# SAMV71_Xplained_Ultra_MCU_Peripherals.net
KiCad netlist of a schematic drawn in Altium Designer
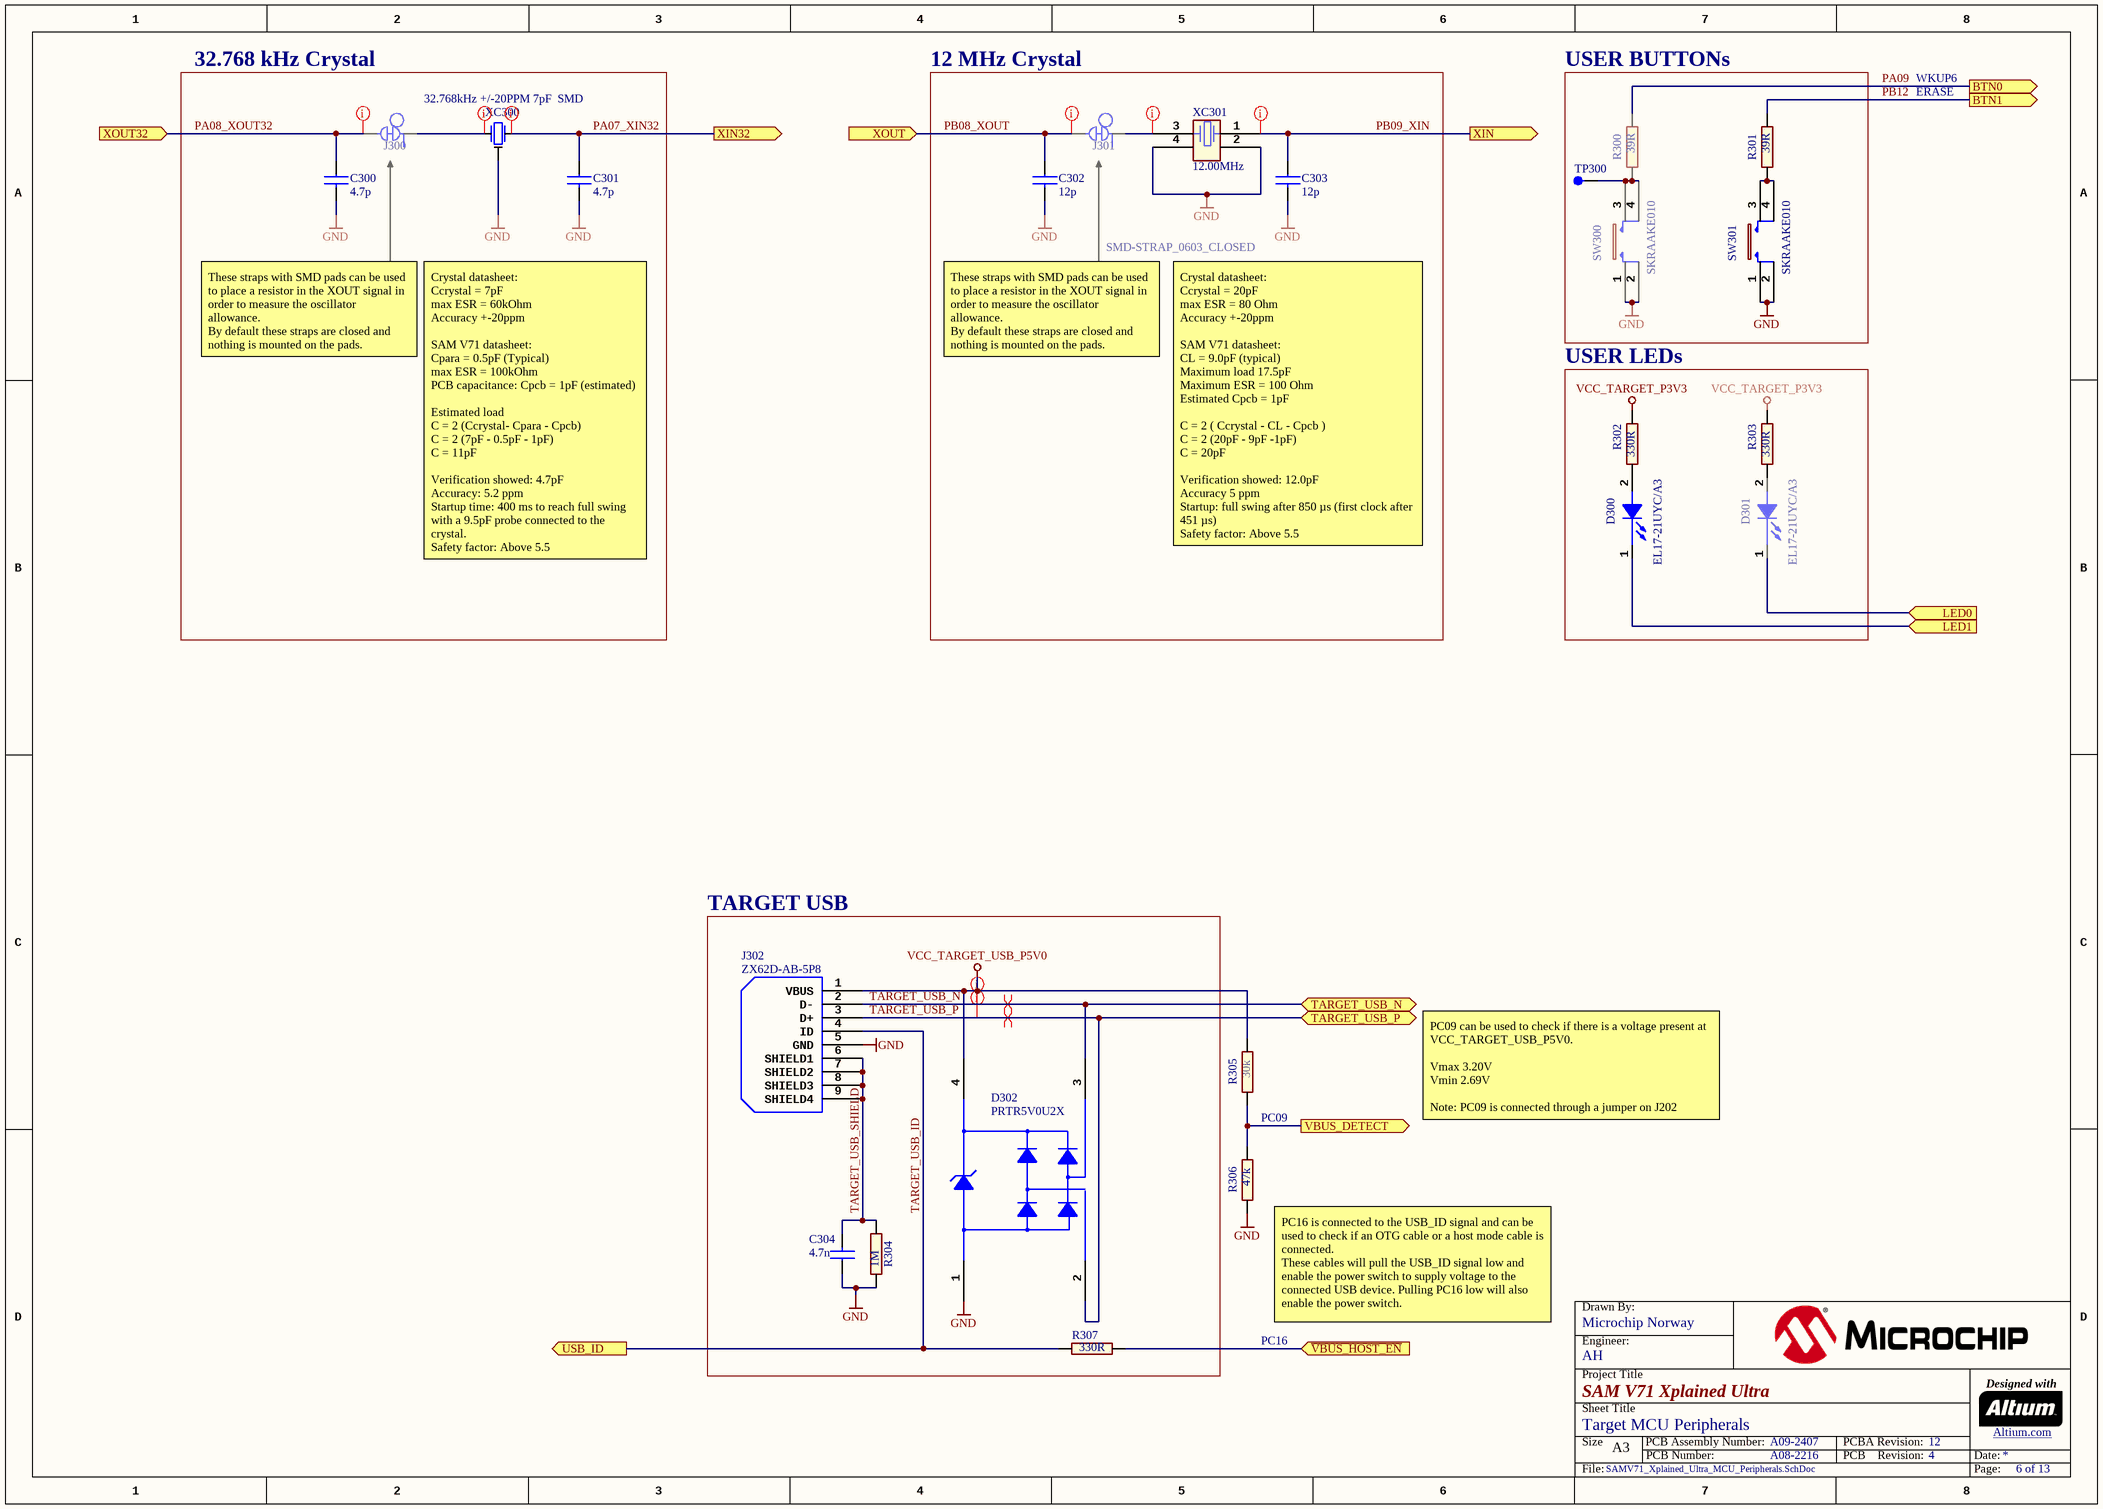
[diagram p0: SAMV71_Xplained_Ultra_MCU_Peripherals.SchDoc]

(export (version "E")
  (design (tool "Eeschema 10.0.6"))
  (components
    (comp (ref "C300")
      (value "4.7p")
      (footprint "AP1-00001")
      (description "Ceramic capacitor, SMD 0402, NP0, 50V, +/-0.25pF")
      (fields (field (name "TOLERANCE") "50V, +/-0.25pF") (field (name "MANUFACTURER") "YAGEO CORP"))
      (libsource (lib "AltiumDbLib") (part "CAP-NONPOL"))
    )
    (comp (ref "C301")
      (value "4.7p")
      (footprint "AP1-00001")
      (description "Ceramic capacitor, SMD 0402, NP0, 50V, +/-0.25pF")
      (fields (field (name "TOLERANCE") "50V, +/-0.25pF") (field (name "MANUFACTURER") "YAGEO CORP"))
      (libsource (lib "AltiumDbLib") (part "CAP-NONPOL"))
    )
    (comp (ref "C302")
      (value "12p")
      (footprint "AP1-00001")
      (description "Ceramic capacitor, SMD 0402, NP0, 50V, +/-5%")
      (fields (field (name "TOLERANCE") "50V, +/-5%") (field (name "MANUFACTURER") "Kemet"))
      (libsource (lib "AltiumDbLib") (part "CAP-NONPOL"))
    )
    (comp (ref "C303")
      (value "12p")
      (footprint "AP1-00001")
      (description "Ceramic capacitor, SMD 0402, NP0, 50V, +/-5%")
      (fields (field (name "TOLERANCE") "50V, +/-5%") (field (name "MANUFACTURER") "Kemet"))
      (libsource (lib "AltiumDbLib") (part "CAP-NONPOL"))
    )
    (comp (ref "C304")
      (value "4.7n")
      (footprint "AP1-00053")
      (description "Ceramic capacitor, SMD 0402, X7R, 25V, +/-10%")
      (fields (field (name "TOLERANCE") "25V, +/-10%") (field (name "MANUFACTURER") "PHYCOMP"))
      (libsource (lib "AltiumDbLib") (part "CAP-NONPOL"))
    )
    (comp (ref "D300")
      (value "EL17-21UYC/A3")
      (footprint "AP4-00013")
      (description "LED, Yellow, Wave length=591nm, SMD 0805, ±70°")
      (fields (field (name "MANUFACTURER") "Everlight") (field (name "MPN") "17-21UYC/S530-A3/TR8"))
      (libsource (lib "AltiumDbLib") (part "LED_12"))
    )
    (comp (ref "D301")
      (value "EL17-21UYC/A3")
      (footprint "AP4-00013")
      (description "LED, Yellow, Wave length=591nm, SMD 0805, ±70°")
      (fields (field (name "MANUFACTURER") "Everlight") (field (name "MPN") "17-21UYC/S530-A3/TR8"))
      (libsource (lib "AltiumDbLib") (part "LED_12"))
    )
    (comp (ref "D302")
      (value "PRTR5V0U2X")
      (footprint "AP4-00001")
      (description "Double rail-to-rail USB ESD protection diode")
      (fields (field (name "MANUFACTURER") "NXP"))
      (libsource (lib "AltiumDbLib") (part "PRTR5V0U2X"))
    )
    (comp (ref "J300")
      (value "~")
      (footprint "AP9-00044")
      (description "Default closed SMD strap, 0603 size")
      (libsource (lib "AltiumDbLib") (part "SMD-STRAP_CLOSED"))
    )
    (comp (ref "J301")
      (value "SMD-STRAP_0603_CLOSED")
      (footprint "AP9-00044")
      (description "Default closed SMD strap, 0603 size")
      (libsource (lib "AltiumDbLib") (part "SMD-STRAP_CLOSED"))
    )
    (comp (ref "J302")
      (value "ZX62D-AB-5P8")
      (footprint "AP8-00852")
      (description "Micro USB AB Connector, Standard SMT + DIP")
      (fields (field (name "MANUFACTURER") "HIROSE") (field (name "MPN") "ZX62D-AB-5P8(30)"))
      (libsource (lib "AltiumDbLib") (part "USB_AB"))
    )
    (comp (ref "R300")
      (value "39R")
      (footprint "AP2-00011")
      (description "Thick film resistor, SMD 0402, 1/16W, 1%")
      (fields (field (name "TOLERANCE") "1 %") (field (name "MANUFACTURER") "ASJ"))
      (libsource (lib "") (part "R2_1"))
    )
    (comp (ref "R301")
      (value "39R")
      (footprint "AP2-00011")
      (description "Thick film resistor, SMD 0402, 1/16W, 1%")
      (fields (field (name "TOLERANCE") "1 %") (field (name "MANUFACTURER") "ASJ"))
      (libsource (lib "") (part "R2_1"))
    )
    (comp (ref "R302")
      (value "330R")
      (footprint "AP2-00000")
      (description "Thick film resistor, SMD 0402, 1/16W, 1%")
      (fields (field (name "TOLERANCE") "1 %") (field (name "MANUFACTURER") "ASJ"))
      (libsource (lib "AltiumDbLib") (part "R2"))
    )
    (comp (ref "R303")
      (value "330R")
      (footprint "AP2-00000")
      (description "Thick film resistor, SMD 0402, 1/16W, 1%")
      (fields (field (name "TOLERANCE") "1 %") (field (name "MANUFACTURER") "ASJ"))
      (libsource (lib "AltiumDbLib") (part "R2"))
    )
    (comp (ref "R304")
      (value "1M")
      (footprint "AP2-00011")
      (description "Thick film resistor, SMD 0402, 1/16W, 1%")
      (fields (field (name "TOLERANCE") "1 %") (field (name "MANUFACTURER") "ASJ"))
      (libsource (lib "") (part "R2_1"))
    )
    (comp (ref "R305")
      (value "30k")
      (footprint "AP2-00000")
      (description "Thick film resistor, SMD 0402, 1/16W, 1%")
      (fields (field (name "TOLERANCE") "1 %") (field (name "MANUFACTURER") "ASJ"))
      (libsource (lib "AltiumDbLib") (part "R2"))
    )
    (comp (ref "R306")
      (value "47k")
      (footprint "AP2-00000")
      (description "Thick film resistor, SMD 0402, 1/16W, 1%")
      (fields (field (name "TOLERANCE") "1 %") (field (name "MANUFACTURER") "KOA"))
      (libsource (lib "AltiumDbLib") (part "R2"))
    )
    (comp (ref "R307")
      (value "330R")
      (footprint "AP2-00000")
      (description "Thick film resistor, SMD 0402, 1/16W, 1%")
      (fields (field (name "TOLERANCE") "1 %") (field (name "MANUFACTURER") "ASJ"))
      (libsource (lib "") (part "R2_2"))
    )
    (comp (ref "SW300")
      (value "SKRAAKE010")
      (footprint "AP8-00137")
      (description "6.2x6.2 mm SMD tact switch, same as A08-0091 but less force is needed")
      (fields (field (name "MANUFACTURER") "ALPS"))
      (libsource (lib "AltiumDbLib") (part "PUSHBUTTON1"))
    )
    (comp (ref "SW301")
      (value "SKRAAKE010")
      (footprint "AP8-00137")
      (description "6.2x6.2 mm SMD tact switch, same as A08-0091 but less force is needed")
      (fields (field (name "MANUFACTURER") "ALPS"))
      (libsource (lib "AltiumDbLib") (part "PUSHBUTTON1"))
    )
    (comp (ref "TP300")
      (value "~")
      (footprint "AP8-00010")
      (description "Single SMD testpad")
      (libsource (lib "AltiumDbLib") (part "TESTPOINT"))
    )
    (comp (ref "XC300")
      (value "32.768kHz +/-20PPM 7pF  SMD")
      (footprint "AP7-00044")
      (description "32k768 crystal, +-20ppm, CL=7pF, max ESR 60kOhm, SMD")
      (fields (field (name "TOLERANCE") "+/- 20 PPM") (field (name "MANUFACTURER") "Micro Crystal"))
      (libsource (lib "AltiumDbLib") (part "CRYSTAL_2P_metal"))
    )
    (comp (ref "XC301")
      (value "12.00MHz")
      (footprint "AP7-00039")
      (description "Fox FQ5032B 12.0MHz SMD crystal 738B-12")
      (fields (field (name "TOLERANCE") "Â±30ppm") (field (name "MANUFACTURER") "Fox  Electronics"))
      (libsource (lib "AltiumDbLib") (part "CRYSTAL1324"))
    )
  )
  (nets
    (net (code "1") (name "/LED0") (class "Default")
      (node (ref "D301") (pin "1") (pinfunction "CATHODE_1") (pintype "passive"))
    )
    (net (code "2") (name "/LED1") (class "Default")
      (node (ref "D300") (pin "1") (pinfunction "CATHODE_1") (pintype "passive"))
    )
    (net (code "3") (name "/PA07_XIN32") (class "Default")
      (node (ref "C301") (pin "1") (pinfunction "1_1") (pintype "passive"))
      (node (ref "XC300") (pin "2") (pinfunction "2_2") (pintype "passive"))
    )
    (net (code "4") (name "/PA08_XOUT32") (class "Default")
      (node (ref "C300") (pin "1") (pinfunction "1_1") (pintype "passive"))
      (node (ref "J300") (pin "2") (pinfunction "2_2") (pintype "passive"))
    )
    (net (code "5") (name "/PA09") (class "Default")
      (node (ref "R300") (pin "2") (pinfunction "2_2") (pintype "passive"))
    )
    (net (code "6") (name "/PB08_XOUT") (class "Default")
      (node (ref "C302") (pin "1") (pinfunction "1_1") (pintype "passive"))
      (node (ref "J301") (pin "2") (pinfunction "2_2") (pintype "passive"))
    )
    (net (code "7") (name "/PB09_XIN") (class "Default")
      (node (ref "C303") (pin "1") (pinfunction "1_1") (pintype "passive"))
      (node (ref "XC301") (pin "1") (pinfunction "1_1") (pintype "passive"))
    )
    (net (code "8") (name "/PB12") (class "Default")
      (node (ref "R301") (pin "2") (pinfunction "2_2") (pintype "passive"))
    )
    (net (code "9") (name "/TARGET_USB_ID") (class "Default")
      (node (ref "J302") (pin "4") (pinfunction "ID_4") (pintype "passive"))
      (node (ref "R307") (pin "1") (pinfunction "1_1") (pintype "passive"))
    )
    (net (code "10") (name "/TARGET_USB_N") (class "Default")
      (node (ref "D302") (pin "3") (pinfunction "I/O_2_3") (pintype "passive"))
      (node (ref "J302") (pin "2") (pinfunction "D-_2") (pintype "passive"))
    )
    (net (code "11") (name "/TARGET_USB_P") (class "Default")
      (node (ref "D302") (pin "2") (pinfunction "I/O_1_2") (pintype "passive"))
      (node (ref "J302") (pin "3") (pinfunction "D+_3") (pintype "passive"))
    )
    (net (code "12") (name "/TARGET_USB_SHIELD") (class "Default")
      (node (ref "C304") (pin "2") (pinfunction "2_2") (pintype "passive"))
      (node (ref "J302") (pin "6") (pinfunction "SHIELD1_6") (pintype "passive"))
      (node (ref "J302") (pin "7") (pinfunction "SHIELD2_7") (pintype "passive"))
      (node (ref "J302") (pin "8") (pinfunction "SHIELD3_8") (pintype "passive"))
      (node (ref "J302") (pin "9") (pinfunction "SHIELD4_9") (pintype "passive"))
      (node (ref "R304") (pin "2") (pinfunction "2_2") (pintype "passive"))
    )
    (net (code "13") (name "/VBUS_DETECT") (class "Default")
      (node (ref "R305") (pin "1") (pinfunction "1_1") (pintype "passive"))
      (node (ref "R306") (pin "2") (pinfunction "2_2") (pintype "passive"))
    )
    (net (code "14") (name "/~{VBUS_HOST_EN}") (class "Default")
      (node (ref "R307") (pin "2") (pinfunction "2_2") (pintype "passive"))
    )
    (net (code "15") (name "GND") (class "Default")
      (node (ref "C300") (pin "2") (pinfunction "2_2") (pintype "passive"))
      (node (ref "C301") (pin "2") (pinfunction "2_2") (pintype "passive"))
      (node (ref "C302") (pin "2") (pinfunction "2_2") (pintype "passive"))
      (node (ref "C303") (pin "2") (pinfunction "2_2") (pintype "passive"))
      (node (ref "C304") (pin "1") (pinfunction "1_1") (pintype "passive"))
      (node (ref "D302") (pin "1") (pinfunction "GND_1") (pintype "passive"))
      (node (ref "J302") (pin "5") (pinfunction "GND_5") (pintype "passive"))
      (node (ref "R304") (pin "1") (pinfunction "1_1") (pintype "passive"))
      (node (ref "R306") (pin "1") (pinfunction "1_1") (pintype "passive"))
      (node (ref "SW300") (pin "1") (pinfunction "1_1") (pintype "passive"))
      (node (ref "SW300") (pin "2") (pinfunction "2_2") (pintype "passive"))
      (node (ref "SW301") (pin "1") (pinfunction "1_1") (pintype "passive"))
      (node (ref "SW301") (pin "2") (pinfunction "2_2") (pintype "passive"))
      (node (ref "XC300") (pin "3") (pinfunction "3_3") (pintype "passive"))
      (node (ref "XC301") (pin "2") (pinfunction "2_2") (pintype "passive"))
      (node (ref "XC301") (pin "4") (pinfunction "4_4") (pintype "passive"))
    )
    (net (code "16") (name "Net-(D300-ANODE)") (class "Default")
      (node (ref "D300") (pin "2") (pinfunction "ANODE_2") (pintype "passive"))
      (node (ref "R302") (pin "1") (pinfunction "1_1") (pintype "passive"))
    )
    (net (code "17") (name "Net-(D301-ANODE)") (class "Default")
      (node (ref "D301") (pin "2") (pinfunction "ANODE_2") (pintype "passive"))
      (node (ref "R303") (pin "1") (pinfunction "1_1") (pintype "passive"))
    )
    (net (code "18") (name "Net-(J300-Pad1)") (class "Default")
      (node (ref "J300") (pin "1") (pinfunction "1_1") (pintype "passive"))
      (node (ref "XC300") (pin "1") (pinfunction "1_1") (pintype "passive"))
    )
    (net (code "19") (name "Net-(J301-Pad1)") (class "Default")
      (node (ref "J301") (pin "1") (pinfunction "1_1") (pintype "passive"))
      (node (ref "XC301") (pin "3") (pinfunction "3_3") (pintype "passive"))
    )
    (net (code "20") (name "Net-(R300-Pad1)") (class "Default")
      (node (ref "R300") (pin "1") (pinfunction "1_1") (pintype "passive"))
      (node (ref "SW300") (pin "3") (pinfunction "3_3") (pintype "passive"))
      (node (ref "SW300") (pin "4") (pinfunction "4_4") (pintype "passive"))
      (node (ref "TP300") (pin "1") (pinfunction "1_1") (pintype "passive"))
    )
    (net (code "21") (name "Net-(R301-Pad1)") (class "Default")
      (node (ref "R301") (pin "1") (pinfunction "1_1") (pintype "passive"))
      (node (ref "SW301") (pin "3") (pinfunction "3_3") (pintype "passive"))
      (node (ref "SW301") (pin "4") (pinfunction "4_4") (pintype "passive"))
    )
    (net (code "22") (name "VCC_TARGET_P3V3") (class "Default")
      (node (ref "R302") (pin "2") (pinfunction "2_2") (pintype "passive"))
      (node (ref "R303") (pin "2") (pinfunction "2_2") (pintype "passive"))
    )
    (net (code "23") (name "VCC_TARGET_USB_P5V0") (class "Default")
      (node (ref "D302") (pin "4") (pinfunction "VCC_4") (pintype "passive"))
      (node (ref "J302") (pin "1") (pinfunction "VBUS_1") (pintype "passive"))
      (node (ref "R305") (pin "2") (pinfunction "2_2") (pintype "passive"))
    )
  )
)
